# pcb_power.net
KiCad netlist of a schematic drawn in EAGLE
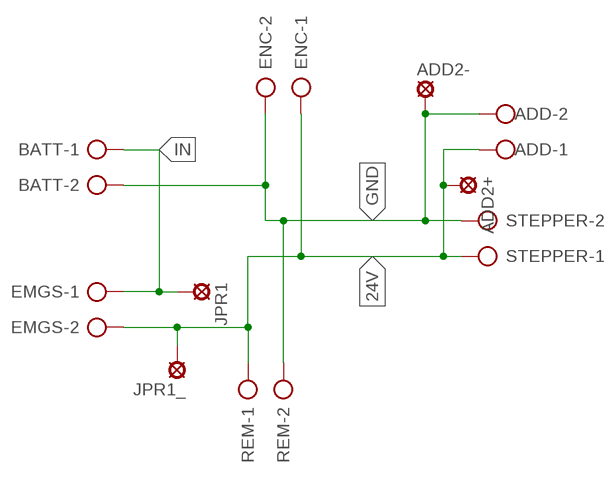
[diagram p0: schematic, sheet 1]

(export (version "E")
  (design (tool "Eeschema 10.0.6"))
  (components
    (comp (ref "ADD")
      (value "W237-102")
      (footprint "eagle-import:W237-102")
      (fields (field (name "MPN") "237-102"))
      (libsource (lib "eagle-import") (part "W237-102"))
    )
    (comp (ref "ADD2+")
      (value "SE14")
      (footprint "eagle-import:SE14")
      (libsource (lib "eagle-import") (part "SE14"))
    )
    (comp (ref "ADD2-")
      (value "SE14")
      (footprint "eagle-import:SE14")
      (libsource (lib "eagle-import") (part "SE14"))
    )
    (comp (ref "BATT")
      (value "W237-102")
      (footprint "eagle-import:W237-102")
      (fields (field (name "MPN") "237-102"))
      (libsource (lib "eagle-import") (part "W237-102"))
    )
    (comp (ref "EMGS")
      (value "W237-102")
      (footprint "eagle-import:W237-102")
      (fields (field (name "MPN") "237-102"))
      (libsource (lib "eagle-import") (part "W237-102"))
    )
    (comp (ref "ENC")
      (value "W237-102")
      (footprint "eagle-import:W237-102")
      (fields (field (name "MPN") "237-102"))
      (libsource (lib "eagle-import") (part "W237-102"))
    )
    (comp (ref "JPR1")
      (value "SE14")
      (footprint "eagle-import:SE14")
      (libsource (lib "eagle-import") (part "SE14"))
    )
    (comp (ref "JPR1_")
      (value "SE14")
      (footprint "eagle-import:SE14")
      (libsource (lib "eagle-import") (part "SE14"))
    )
    (comp (ref "REM")
      (value "W237-102")
      (footprint "eagle-import:W237-102")
      (fields (field (name "MPN") "237-102"))
      (libsource (lib "eagle-import") (part "W237-102"))
    )
    (comp (ref "STEPPER")
      (value "W237-102")
      (footprint "eagle-import:W237-102")
      (fields (field (name "MPN") "237-102"))
      (libsource (lib "eagle-import") (part "W237-102"))
    )
  )
  (nets
    (net (code "1") (name "24V") (class "Default")
      (node (ref "ADD") (pin "1") (pinfunction "KL_1") (pintype "passive"))
      (node (ref "ADD2+") (pin "MP") (pinfunction "MP_MP") (pintype "passive"))
      (node (ref "EMGS") (pin "2") (pinfunction "KL_2") (pintype "passive"))
      (node (ref "ENC") (pin "1") (pinfunction "KL_1") (pintype "passive"))
      (node (ref "JPR1_") (pin "MP") (pinfunction "MP_MP") (pintype "passive"))
      (node (ref "REM") (pin "1") (pinfunction "KL_1") (pintype "passive"))
      (node (ref "STEPPER") (pin "1") (pinfunction "KL_1") (pintype "passive"))
    )
    (net (code "2") (name "GND") (class "Default")
      (node (ref "ADD") (pin "2") (pinfunction "KL_2") (pintype "passive"))
      (node (ref "ADD2-") (pin "MP") (pinfunction "MP_MP") (pintype "passive"))
      (node (ref "BATT") (pin "2") (pinfunction "KL_2") (pintype "passive"))
      (node (ref "ENC") (pin "2") (pinfunction "KL_2") (pintype "passive"))
      (node (ref "REM") (pin "2") (pinfunction "KL_2") (pintype "passive"))
      (node (ref "STEPPER") (pin "2") (pinfunction "KL_2") (pintype "passive"))
    )
    (net (code "3") (name "IN") (class "Default")
      (node (ref "BATT") (pin "1") (pinfunction "KL_1") (pintype "passive"))
      (node (ref "EMGS") (pin "1") (pinfunction "KL_1") (pintype "passive"))
      (node (ref "JPR1") (pin "MP") (pinfunction "MP_MP") (pintype "passive"))
    )
  )
)
